# tarjeta2.net
KiCad netlist of a schematic drawn in EAGLE
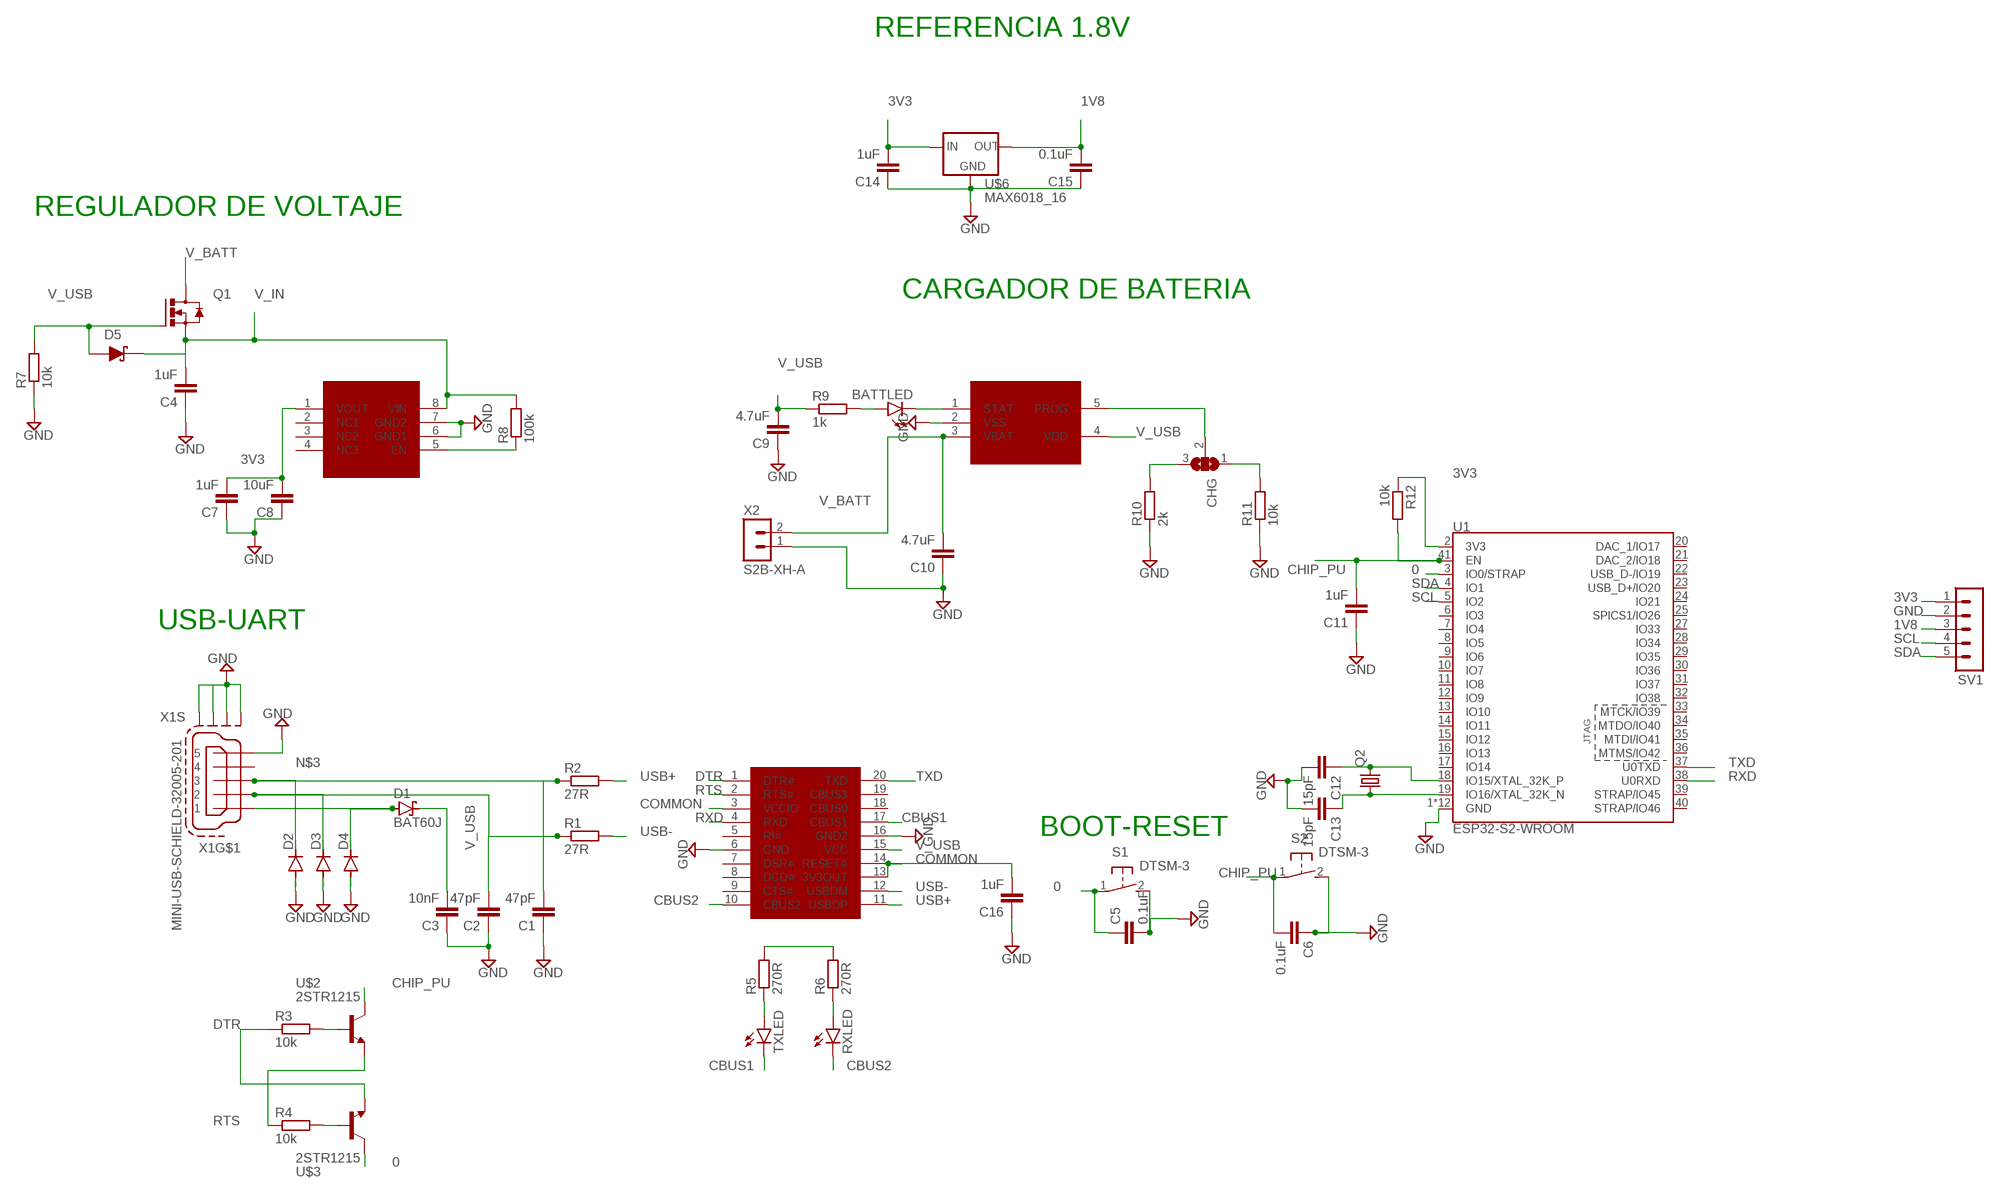
[diagram p0: schematic, sheet 1]

(export (version "E")
  (design (tool "Eeschema 10.0.6"))
  (components
    (comp (ref "BATTLED")
      (value "LEDSML0603")
      (footprint "eagle-import:SML0603")
      (libsource (lib "eagle-import") (part "LEDSML0603"))
    )
    (comp (ref "C1")
      (value "47pF")
      (footprint "eagle-import:C0805")
      (libsource (lib "eagle-import") (part "C-EUC0805"))
    )
    (comp (ref "C2")
      (value "47pF")
      (footprint "eagle-import:C0805")
      (libsource (lib "eagle-import") (part "C-EUC0805"))
    )
    (comp (ref "C3")
      (value "10nF")
      (footprint "eagle-import:C0805")
      (libsource (lib "eagle-import") (part "C-EUC0805"))
    )
    (comp (ref "C4")
      (value "1uF")
      (footprint "eagle-import:C0805")
      (libsource (lib "eagle-import") (part "C-EUC0805"))
    )
    (comp (ref "C5")
      (value "0.1uF")
      (footprint "eagle-import:C0805")
      (libsource (lib "eagle-import") (part "C-EUC0805"))
    )
    (comp (ref "C6")
      (value "0.1uF")
      (footprint "eagle-import:C0805")
      (libsource (lib "eagle-import") (part "C-EUC0805"))
    )
    (comp (ref "C7")
      (value "1uF")
      (footprint "eagle-import:C0805")
      (libsource (lib "eagle-import") (part "C-EUC0805"))
    )
    (comp (ref "C8")
      (value "10uF")
      (footprint "eagle-import:C0805")
      (libsource (lib "eagle-import") (part "C-EUC0805"))
    )
    (comp (ref "C9")
      (value "4.7uF")
      (footprint "eagle-import:C0805")
      (libsource (lib "eagle-import") (part "C-EUC0805"))
    )
    (comp (ref "C10")
      (value "4.7uF")
      (footprint "eagle-import:C0805")
      (libsource (lib "eagle-import") (part "C-EUC0805"))
    )
    (comp (ref "C11")
      (value "1uF")
      (footprint "eagle-import:C0805")
      (libsource (lib "eagle-import") (part "C-EUC0805"))
    )
    (comp (ref "C12")
      (value "15pF")
      (footprint "eagle-import:C0805")
      (libsource (lib "eagle-import") (part "C-EUC0805"))
    )
    (comp (ref "C13")
      (value "15pF")
      (footprint "eagle-import:C0805")
      (libsource (lib "eagle-import") (part "C-EUC0805"))
    )
    (comp (ref "C14")
      (value "1uF")
      (footprint "eagle-import:C0805")
      (libsource (lib "eagle-import") (part "C-EUC0805"))
    )
    (comp (ref "C15")
      (value "0.1uF")
      (footprint "eagle-import:C0805")
      (libsource (lib "eagle-import") (part "C-EUC0805"))
    )
    (comp (ref "C16")
      (value "1uF")
      (footprint "eagle-import:C0805")
      (libsource (lib "eagle-import") (part "C-EUC0805"))
    )
    (comp (ref "CHG")
      (value "SJ2W")
      (footprint "eagle-import:SJ_2")
      (libsource (lib "eagle-import") (part "SJ2W"))
    )
    (comp (ref "D1")
      (value "BAT60J")
      (footprint "eagle-import:SOD323_ST")
      (libsource (lib "eagle-import") (part "BAT60J"))
    )
    (comp (ref "D2")
      (value "DIODE-SOD523")
      (footprint "eagle-import:SOD523")
      (libsource (lib "eagle-import") (part "DIODE-SOD523"))
    )
    (comp (ref "D3")
      (value "DIODE-SOD523")
      (footprint "eagle-import:SOD523")
      (libsource (lib "eagle-import") (part "DIODE-SOD523"))
    )
    (comp (ref "D4")
      (value "DIODE-SOD523")
      (footprint "eagle-import:SOD523")
      (libsource (lib "eagle-import") (part "DIODE-SOD523"))
    )
    (comp (ref "D5")
      (value "D_SCHOTTKYK")
      (footprint "eagle-import:SOD-123")
      (libsource (lib "eagle-import") (part "D_SCHOTTKYK"))
    )
    (comp (ref "Q1")
      (value "MOSFET_N_SOT231")
      (footprint "eagle-import:SOT23")
      (libsource (lib "eagle-import") (part "MOSFET_N_SOT231"))
    )
    (comp (ref "Q2")
      (value "CRYSTALTC26V")
      (footprint "eagle-import:TC26V")
      (libsource (lib "eagle-import") (part "CRYSTALTC26V"))
    )
    (comp (ref "R1")
      (value "27R")
      (footprint "eagle-import:R0805")
      (libsource (lib "eagle-import") (part "R-EU_R0805"))
    )
    (comp (ref "R2")
      (value "27R")
      (footprint "eagle-import:R0805")
      (libsource (lib "eagle-import") (part "R-EU_R0805"))
    )
    (comp (ref "R3")
      (value "10k")
      (footprint "eagle-import:R0805")
      (libsource (lib "eagle-import") (part "R-EU_R0805"))
    )
    (comp (ref "R4")
      (value "10k")
      (footprint "eagle-import:R0805")
      (libsource (lib "eagle-import") (part "R-EU_R0805"))
    )
    (comp (ref "R5")
      (value "270R")
      (footprint "eagle-import:R0805")
      (libsource (lib "eagle-import") (part "R-EU_R0805"))
    )
    (comp (ref "R6")
      (value "270R")
      (footprint "eagle-import:R0805")
      (libsource (lib "eagle-import") (part "R-EU_R0805"))
    )
    (comp (ref "R7")
      (value "10k")
      (footprint "eagle-import:R0805")
      (libsource (lib "eagle-import") (part "R-EU_R0805"))
    )
    (comp (ref "R8")
      (value "100k")
      (footprint "eagle-import:R0805")
      (libsource (lib "eagle-import") (part "R-EU_R0805"))
    )
    (comp (ref "R9")
      (value "1k")
      (footprint "eagle-import:R0805")
      (libsource (lib "eagle-import") (part "R-EU_R0805"))
    )
    (comp (ref "R10")
      (value "2k")
      (footprint "eagle-import:R0805")
      (libsource (lib "eagle-import") (part "R-EU_R0805"))
    )
    (comp (ref "R11")
      (value "10k")
      (footprint "eagle-import:R0805")
      (libsource (lib "eagle-import") (part "R-EU_R0805"))
    )
    (comp (ref "R12")
      (value "10k")
      (footprint "eagle-import:R0805")
      (libsource (lib "eagle-import") (part "R-EU_R0805"))
    )
    (comp (ref "RXLED")
      (value "LEDSML0603")
      (footprint "eagle-import:SML0603")
      (libsource (lib "eagle-import") (part "LEDSML0603"))
    )
    (comp (ref "S1")
      (value "DTSM-3")
      (footprint "eagle-import:DTSM-3")
      (libsource (lib "eagle-import") (part "DTSM-3"))
    )
    (comp (ref "S2")
      (value "DTSM-3")
      (footprint "eagle-import:DTSM-3")
      (libsource (lib "eagle-import") (part "DTSM-3"))
    )
    (comp (ref "SV1")
      (value "MA05-1")
      (footprint "eagle-import:MA05-1")
      (libsource (lib "eagle-import") (part "MA05-1"))
    )
    (comp (ref "TXLED")
      (value "LEDSML0603")
      (footprint "eagle-import:SML0603")
      (libsource (lib "eagle-import") (part "LEDSML0603"))
    )
    (comp (ref "U$1")
      (value "FT231XS-R")
      (footprint "eagle-import:SSOP20")
      (libsource (lib "eagle-import") (part "FT231XS-R"))
    )
    (comp (ref "U$2")
      (value "2STR1215")
      (footprint "eagle-import:SOT23")
      (libsource (lib "eagle-import") (part "2STR1215"))
    )
    (comp (ref "U$3")
      (value "2STR1215")
      (footprint "eagle-import:SOT23")
      (libsource (lib "eagle-import") (part "2STR1215"))
    )
    (comp (ref "U$4")
      (value "AP2112-3.3")
      (footprint "eagle-import:SOIC8")
      (libsource (lib "eagle-import") (part "AP2112-3.3"))
    )
    (comp (ref "U$5")
      (value "MCP73831/2")
      (footprint "eagle-import:SOT23-5")
      (libsource (lib "eagle-import") (part "MCP73831/2"))
    )
    (comp (ref "U$6")
      (value "MAX6018_16")
      (footprint "eagle-import:SOT23")
      (libsource (lib "eagle-import") (part "MAX6018_16"))
    )
    (comp (ref "U1")
      (value "ESP32-S2-WROOM")
      (footprint "eagle-import:ESP32-S2-WROOM")
      (libsource (lib "eagle-import") (part "ESP32-S2-WROOM"))
    )
    (comp (ref "X1")
      (value "MINI-USB-SCHIELD-32005-201")
      (footprint "eagle-import:32005-201")
      (libsource (lib "eagle-import") (part "MINI-USB-SCHIELD-32005-201"))
    )
    (comp (ref "X2")
      (value "S2B-XH-A")
      (footprint "eagle-import:S2B-XH-A")
      (libsource (lib "eagle-import") (part "S2B-XH-A"))
    )
  )
  (nets
    (net (code "1") (name "/0") (class "Default")
      (node (ref "C5") (pin "1") (pinfunction "1_1") (pintype "passive"))
      (node (ref "S1") (pin "1") (pinfunction "1_1") (pintype "passive"))
      (node (ref "U$3") (pin "3") (pinfunction "C_3") (pintype "passive"))
      (node (ref "U1") (pin "3") (pinfunction "IO0/STRAP_3") (pintype "bidirectional"))
    )
    (net (code "2") (name "/1V8") (class "Default")
      (node (ref "C15") (pin "2") (pinfunction "2_2") (pintype "passive"))
      (node (ref "SV1") (pin "3") (pinfunction "3_3") (pintype "passive"))
      (node (ref "U$6") (pin "2") (pinfunction "OUT_2") (pintype "passive"))
    )
    (net (code "3") (name "/3V3") (class "Default")
      (node (ref "C14") (pin "2") (pinfunction "2_2") (pintype "passive"))
      (node (ref "C7") (pin "2") (pinfunction "2_2") (pintype "passive"))
      (node (ref "C8") (pin "2") (pinfunction "2_2") (pintype "passive"))
      (node (ref "R12") (pin "1") (pinfunction "1_1") (pintype "passive"))
      (node (ref "SV1") (pin "1") (pinfunction "1_1") (pintype "passive"))
      (node (ref "U$4") (pin "1") (pinfunction "VOUT_1") (pintype "bidirectional"))
      (node (ref "U$6") (pin "1") (pinfunction "IN_1") (pintype "input"))
      (node (ref "U1") (pin "2") (pinfunction "3V3_2") (pintype "bidirectional"))
    )
    (net (code "4") (name "/CBUS1") (class "Default")
      (node (ref "TXLED") (pin "C") (pinfunction "C_C") (pintype "passive"))
      (node (ref "U$1") (pin "17") (pinfunction "CBUS1_17") (pintype "bidirectional"))
    )
    (net (code "5") (name "/CBUS2") (class "Default")
      (node (ref "RXLED") (pin "C") (pinfunction "C_C") (pintype "passive"))
      (node (ref "U$1") (pin "10") (pinfunction "CBUS2_10") (pintype "bidirectional"))
    )
    (net (code "6") (name "/CHIP_PU") (class "Default")
      (node (ref "C11") (pin "2") (pinfunction "2_2") (pintype "passive"))
      (node (ref "C6") (pin "2") (pinfunction "2_2") (pintype "passive"))
      (node (ref "R12") (pin "2") (pinfunction "2_2") (pintype "passive"))
      (node (ref "S2") (pin "1") (pinfunction "1_1") (pintype "passive"))
      (node (ref "U$2") (pin "3") (pinfunction "C_3") (pintype "passive"))
      (node (ref "U1") (pin "41") (pinfunction "EN_41") (pintype "bidirectional"))
    )
    (net (code "7") (name "/COMMON") (class "Default")
      (node (ref "C16") (pin "2") (pinfunction "2_2") (pintype "passive"))
      (node (ref "U$1") (pin "13") (pinfunction "3V3OUT_13") (pintype "bidirectional"))
      (node (ref "U$1") (pin "14") (pinfunction "RESET#_14") (pintype "bidirectional"))
      (node (ref "U$1") (pin "3") (pinfunction "VCCIO_3") (pintype "bidirectional"))
    )
    (net (code "8") (name "/DTR") (class "Default")
      (node (ref "R3") (pin "1") (pinfunction "1_1") (pintype "passive"))
      (node (ref "U$1") (pin "1") (pinfunction "DTR#_1") (pintype "bidirectional"))
      (node (ref "U$3") (pin "2") (pinfunction "E_2") (pintype "passive"))
    )
    (net (code "9") (name "/N$3") (class "Default")
      (node (ref "C1") (pin "2") (pinfunction "2_2") (pintype "passive"))
      (node (ref "D2") (pin "C") (pinfunction "C_C") (pintype "passive"))
      (node (ref "R2") (pin "1") (pinfunction "1_1") (pintype "passive"))
      (node (ref "X1") (pin "3") (pinfunction "3_3") (pintype "passive"))
    )
    (net (code "10") (name "/RTS") (class "Default")
      (node (ref "R4") (pin "1") (pinfunction "1_1") (pintype "passive"))
      (node (ref "U$1") (pin "2") (pinfunction "RTS#_2") (pintype "bidirectional"))
      (node (ref "U$2") (pin "2") (pinfunction "E_2") (pintype "passive"))
    )
    (net (code "11") (name "/RXD") (class "Default")
      (node (ref "U$1") (pin "4") (pinfunction "RXD_4") (pintype "bidirectional"))
      (node (ref "U1") (pin "38") (pinfunction "U0RXD_38") (pintype "bidirectional"))
    )
    (net (code "12") (name "/SCL") (class "Default")
      (node (ref "SV1") (pin "4") (pinfunction "4_4") (pintype "passive"))
      (node (ref "U1") (pin "5") (pinfunction "IO2_5") (pintype "bidirectional"))
    )
    (net (code "13") (name "/SDA") (class "Default")
      (node (ref "SV1") (pin "5") (pinfunction "5_5") (pintype "passive"))
      (node (ref "U1") (pin "4") (pinfunction "IO1_4") (pintype "bidirectional"))
    )
    (net (code "14") (name "/TXD") (class "Default")
      (node (ref "U$1") (pin "20") (pinfunction "TXD_20") (pintype "bidirectional"))
      (node (ref "U1") (pin "37") (pinfunction "U0TXD_37") (pintype "bidirectional"))
    )
    (net (code "15") (name "/USB+") (class "Default")
      (node (ref "R2") (pin "2") (pinfunction "2_2") (pintype "passive"))
      (node (ref "U$1") (pin "11") (pinfunction "USBDP_11") (pintype "bidirectional"))
    )
    (net (code "16") (name "/USB-") (class "Default")
      (node (ref "R1") (pin "2") (pinfunction "2_2") (pintype "passive"))
      (node (ref "U$1") (pin "12") (pinfunction "USBDM_12") (pintype "bidirectional"))
    )
    (net (code "17") (name "/V_BATT") (class "Default")
      (node (ref "C10") (pin "2") (pinfunction "2_2") (pintype "passive"))
      (node (ref "Q1") (pin "3") (pinfunction "D_3") (pintype "passive"))
      (node (ref "U$5") (pin "3") (pinfunction "VBAT_3") (pintype "bidirectional"))
      (node (ref "X2") (pin "2") (pinfunction "2_2") (pintype "passive"))
    )
    (net (code "18") (name "/V_IN") (class "Default")
      (node (ref "C4") (pin "2") (pinfunction "2_2") (pintype "passive"))
      (node (ref "D5") (pin "2") (pinfunction "C_2") (pintype "passive"))
      (node (ref "Q1") (pin "2") (pinfunction "S_2") (pintype "passive"))
      (node (ref "R8") (pin "2") (pinfunction "2_2") (pintype "passive"))
      (node (ref "U$4") (pin "8") (pinfunction "VIN_8") (pintype "bidirectional"))
    )
    (net (code "19") (name "/V_USB") (class "Default")
      (node (ref "C3") (pin "2") (pinfunction "2_2") (pintype "passive"))
      (node (ref "C9") (pin "2") (pinfunction "2_2") (pintype "passive"))
      (node (ref "D1") (pin "C") (pinfunction "C_C") (pintype "passive"))
      (node (ref "D5") (pin "1") (pinfunction "A_1") (pintype "passive"))
      (node (ref "Q1") (pin "1") (pinfunction "G_1") (pintype "passive"))
      (node (ref "R5") (pin "2") (pinfunction "2_2") (pintype "passive"))
      (node (ref "R6") (pin "2") (pinfunction "2_2") (pintype "passive"))
      (node (ref "R7") (pin "2") (pinfunction "2_2") (pintype "passive"))
      (node (ref "R9") (pin "1") (pinfunction "1_1") (pintype "passive"))
      (node (ref "U$1") (pin "15") (pinfunction "VCC_15") (pintype "bidirectional"))
      (node (ref "U$5") (pin "4") (pinfunction "VDD_4") (pintype "bidirectional"))
    )
    (net (code "20") (name "GND") (class "Default")
      (node (ref "C1") (pin "1") (pinfunction "1_1") (pintype "passive"))
      (node (ref "C10") (pin "1") (pinfunction "1_1") (pintype "passive"))
      (node (ref "C11") (pin "1") (pinfunction "1_1") (pintype "passive"))
      (node (ref "C12") (pin "2") (pinfunction "2_2") (pintype "passive"))
      (node (ref "C13") (pin "2") (pinfunction "2_2") (pintype "passive"))
      (node (ref "C14") (pin "1") (pinfunction "1_1") (pintype "passive"))
      (node (ref "C15") (pin "1") (pinfunction "1_1") (pintype "passive"))
      (node (ref "C16") (pin "1") (pinfunction "1_1") (pintype "passive"))
      (node (ref "C2") (pin "1") (pinfunction "1_1") (pintype "passive"))
      (node (ref "C3") (pin "1") (pinfunction "1_1") (pintype "passive"))
      (node (ref "C4") (pin "1") (pinfunction "1_1") (pintype "passive"))
      (node (ref "C5") (pin "2") (pinfunction "2_2") (pintype "passive"))
      (node (ref "C6") (pin "1") (pinfunction "1_1") (pintype "passive"))
      (node (ref "C7") (pin "1") (pinfunction "1_1") (pintype "passive"))
      (node (ref "C8") (pin "1") (pinfunction "1_1") (pintype "passive"))
      (node (ref "C9") (pin "1") (pinfunction "1_1") (pintype "passive"))
      (node (ref "D2") (pin "A") (pinfunction "A_A") (pintype "passive"))
      (node (ref "D3") (pin "A") (pinfunction "A_A") (pintype "passive"))
      (node (ref "D4") (pin "A") (pinfunction "A_A") (pintype "passive"))
      (node (ref "R10") (pin "1") (pinfunction "1_1") (pintype "passive"))
      (node (ref "R11") (pin "1") (pinfunction "1_1") (pintype "passive"))
      (node (ref "R7") (pin "1") (pinfunction "1_1") (pintype "passive"))
      (node (ref "S1") (pin "2") (pinfunction "2_2") (pintype "passive"))
      (node (ref "S2") (pin "2") (pinfunction "2_2") (pintype "passive"))
      (node (ref "SV1") (pin "2") (pinfunction "2_2") (pintype "passive"))
      (node (ref "U$1") (pin "16") (pinfunction "GND2_16") (pintype "bidirectional"))
      (node (ref "U$1") (pin "6") (pinfunction "GND_6") (pintype "bidirectional"))
      (node (ref "U$4") (pin "6") (pinfunction "GND1_6") (pintype "bidirectional"))
      (node (ref "U$4") (pin "7") (pinfunction "GND2_7") (pintype "bidirectional"))
      (node (ref "U$5") (pin "2") (pinfunction "VSS_2") (pintype "bidirectional"))
      (node (ref "U$6") (pin "3") (pinfunction "GND_3") (pintype "input"))
      (node (ref "U1") (pin "1") (pinfunction "GND_1") (pintype "bidirectional"))
      (node (ref "U1") (pin "26") (pinfunction "GND_26") (pintype "bidirectional"))
      (node (ref "U1") (pin "42") (pinfunction "GND_42") (pintype "bidirectional"))
      (node (ref "U1") (pin "GNDEP0") (pinfunction "GND_GNDEP0") (pintype "bidirectional"))
      (node (ref "U1") (pin "GNDEP1") (pinfunction "GND_GNDEP1") (pintype "bidirectional"))
      (node (ref "U1") (pin "GNDEP2") (pinfunction "GND_GNDEP2") (pintype "bidirectional"))
      (node (ref "U1") (pin "GNDEP3") (pinfunction "GND_GNDEP3") (pintype "bidirectional"))
      (node (ref "U1") (pin "GNDEP4") (pinfunction "GND_GNDEP4") (pintype "bidirectional"))
      (node (ref "U1") (pin "GNDEP5") (pinfunction "GND_GNDEP5") (pintype "bidirectional"))
      (node (ref "U1") (pin "GNDEP6") (pinfunction "GND_GNDEP6") (pintype "bidirectional"))
      (node (ref "U1") (pin "GNDEP7") (pinfunction "GND_GNDEP7") (pintype "bidirectional"))
      (node (ref "U1") (pin "GNDEP8") (pinfunction "GND_GNDEP8") (pintype "bidirectional"))
      (node (ref "X1") (pin "5") (pinfunction "5_5") (pintype "passive"))
      (node (ref "X1") (pin "M1") (pinfunction "S1_M1") (pintype "passive"))
      (node (ref "X1") (pin "M2") (pinfunction "S2_M2") (pintype "passive"))
      (node (ref "X1") (pin "M3") (pinfunction "S3_M3") (pintype "passive"))
      (node (ref "X1") (pin "M4") (pinfunction "S4_M4") (pintype "passive"))
      (node (ref "X2") (pin "1") (pinfunction "1_1") (pintype "passive"))
    )
    (net (code "21") (name "Net-(BATTLED-PadA)") (class "Default")
      (node (ref "BATTLED") (pin "A") (pinfunction "A_A") (pintype "passive"))
      (node (ref "R9") (pin "2") (pinfunction "2_2") (pintype "passive"))
    )
    (net (code "22") (name "Net-(C2-Pad2)") (class "Default")
      (node (ref "C2") (pin "2") (pinfunction "2_2") (pintype "passive"))
      (node (ref "D3") (pin "C") (pinfunction "C_C") (pintype "passive"))
      (node (ref "R1") (pin "1") (pinfunction "1_1") (pintype "passive"))
      (node (ref "X1") (pin "2") (pinfunction "2_2") (pintype "passive"))
    )
    (net (code "23") (name "Net-(CHG-Pad1)") (class "Default")
      (node (ref "CHG") (pin "1") (pinfunction "1_1") (pintype "passive"))
      (node (ref "R11") (pin "2") (pinfunction "2_2") (pintype "passive"))
    )
    (net (code "24") (name "Net-(CHG-Pad3)") (class "Default")
      (node (ref "CHG") (pin "3") (pinfunction "3_3") (pintype "passive"))
      (node (ref "R10") (pin "2") (pinfunction "2_2") (pintype "passive"))
    )
    (net (code "25") (name "Net-(D1-PadA)") (class "Default")
      (node (ref "D1") (pin "A") (pinfunction "A_A") (pintype "passive"))
      (node (ref "D4") (pin "C") (pinfunction "C_C") (pintype "passive"))
      (node (ref "X1") (pin "1") (pinfunction "1_1") (pintype "passive"))
    )
    (net (code "26") (name "Net-(R5-Pad1)") (class "Default")
      (node (ref "R5") (pin "1") (pinfunction "1_1") (pintype "passive"))
      (node (ref "TXLED") (pin "A") (pinfunction "A_A") (pintype "passive"))
    )
    (net (code "27") (name "Net-(R6-Pad1)") (class "Default")
      (node (ref "R6") (pin "1") (pinfunction "1_1") (pintype "passive"))
      (node (ref "RXLED") (pin "A") (pinfunction "A_A") (pintype "passive"))
    )
    (net (code "28") (name "Net-(U$2-B)") (class "Default")
      (node (ref "R3") (pin "2") (pinfunction "2_2") (pintype "passive"))
      (node (ref "U$2") (pin "1") (pinfunction "B_1") (pintype "passive"))
    )
    (net (code "29") (name "Net-(U$3-B)") (class "Default")
      (node (ref "R4") (pin "2") (pinfunction "2_2") (pintype "passive"))
      (node (ref "U$3") (pin "1") (pinfunction "B_1") (pintype "passive"))
    )
    (net (code "30") (name "Net-(U$4-EN)") (class "Default")
      (node (ref "R8") (pin "1") (pinfunction "1_1") (pintype "passive"))
      (node (ref "U$4") (pin "5") (pinfunction "EN_5") (pintype "bidirectional"))
    )
    (net (code "31") (name "Net-(U$5-PROG)") (class "Default")
      (node (ref "CHG") (pin "2") (pinfunction "2_2") (pintype "passive"))
      (node (ref "U$5") (pin "5") (pinfunction "PROG_5") (pintype "bidirectional"))
    )
    (net (code "32") (name "Net-(U$5-STAT)") (class "Default")
      (node (ref "BATTLED") (pin "C") (pinfunction "C_C") (pintype "passive"))
      (node (ref "U$5") (pin "1") (pinfunction "STAT_1") (pintype "bidirectional"))
    )
    (net (code "33") (name "Net-(U1-IO15{slash}XTAL_32K_P)") (class "Default")
      (node (ref "C12") (pin "1") (pinfunction "1_1") (pintype "passive"))
      (node (ref "Q2") (pin "2") (pinfunction "2_2") (pintype "passive"))
      (node (ref "U1") (pin "18") (pinfunction "IO15/XTAL_32K_P_18") (pintype "bidirectional"))
    )
    (net (code "34") (name "Net-(U1-IO16{slash}XTAL_32K_N)") (class "Default")
      (node (ref "C13") (pin "1") (pinfunction "1_1") (pintype "passive"))
      (node (ref "Q2") (pin "1") (pinfunction "1_1") (pintype "passive"))
      (node (ref "U1") (pin "19") (pinfunction "IO16/XTAL_32K_N_19") (pintype "bidirectional"))
    )
    (net (code "35") (name "unconnected-(U$1-CBUS0-Pad18)") (class "Default")
      (node (ref "U$1") (pin "18") (pinfunction "CBUS0_18") (pintype "bidirectional"))
    )
    (net (code "36") (name "unconnected-(U$1-CBUS3-Pad19)") (class "Default")
      (node (ref "U$1") (pin "19") (pinfunction "CBUS3_19") (pintype "bidirectional"))
    )
    (net (code "37") (name "unconnected-(U$1-CTS#-Pad9)") (class "Default")
      (node (ref "U$1") (pin "9") (pinfunction "CTS#_9") (pintype "bidirectional"))
    )
    (net (code "38") (name "unconnected-(U$1-DCD#-Pad8)") (class "Default")
      (node (ref "U$1") (pin "8") (pinfunction "DCD#_8") (pintype "bidirectional"))
    )
    (net (code "39") (name "unconnected-(U$1-DSR#-Pad7)") (class "Default")
      (node (ref "U$1") (pin "7") (pinfunction "DSR#_7") (pintype "bidirectional"))
    )
    (net (code "40") (name "unconnected-(U$1-RI#-Pad5)") (class "Default")
      (node (ref "U$1") (pin "5") (pinfunction "RI#_5") (pintype "bidirectional"))
    )
    (net (code "41") (name "unconnected-(U$4-NC1-Pad2)") (class "Default")
      (node (ref "U$4") (pin "2") (pinfunction "NC1_2") (pintype "bidirectional"))
    )
    (net (code "42") (name "unconnected-(U$4-NC2-Pad3)") (class "Default")
      (node (ref "U$4") (pin "3") (pinfunction "NC2_3") (pintype "bidirectional"))
    )
    (net (code "43") (name "unconnected-(U$4-NC3-Pad4)") (class "Default")
      (node (ref "U$4") (pin "4") (pinfunction "NC3_4") (pintype "bidirectional"))
    )
    (net (code "44") (name "unconnected-(U1-DAC_1{slash}IO17-Pad20)") (class "Default")
      (node (ref "U1") (pin "20") (pinfunction "DAC_1/IO17_20") (pintype "bidirectional"))
    )
    (net (code "45") (name "unconnected-(U1-DAC_2{slash}IO18-Pad21)") (class "Default")
      (node (ref "U1") (pin "21") (pinfunction "DAC_2/IO18_21") (pintype "bidirectional"))
    )
    (net (code "46") (name "unconnected-(U1-IO3-Pad6)") (class "Default")
      (node (ref "U1") (pin "6") (pinfunction "IO3_6") (pintype "bidirectional"))
    )
    (net (code "47") (name "unconnected-(U1-IO4-Pad7)") (class "Default")
      (node (ref "U1") (pin "7") (pinfunction "IO4_7") (pintype "bidirectional"))
    )
    (net (code "48") (name "unconnected-(U1-IO5-Pad8)") (class "Default")
      (node (ref "U1") (pin "8") (pinfunction "IO5_8") (pintype "bidirectional"))
    )
    (net (code "49") (name "unconnected-(U1-IO6-Pad9)") (class "Default")
      (node (ref "U1") (pin "9") (pinfunction "IO6_9") (pintype "bidirectional"))
    )
    (net (code "50") (name "unconnected-(U1-IO7-Pad10)") (class "Default")
      (node (ref "U1") (pin "10") (pinfunction "IO7_10") (pintype "bidirectional"))
    )
    (net (code "51") (name "unconnected-(U1-IO8-Pad11)") (class "Default")
      (node (ref "U1") (pin "11") (pinfunction "IO8_11") (pintype "bidirectional"))
    )
    (net (code "52") (name "unconnected-(U1-IO9-Pad12)") (class "Default")
      (node (ref "U1") (pin "12") (pinfunction "IO9_12") (pintype "bidirectional"))
    )
    (net (code "53") (name "unconnected-(U1-IO10-Pad13)") (class "Default")
      (node (ref "U1") (pin "13") (pinfunction "IO10_13") (pintype "bidirectional"))
    )
    (net (code "54") (name "unconnected-(U1-IO11-Pad14)") (class "Default")
      (node (ref "U1") (pin "14") (pinfunction "IO11_14") (pintype "bidirectional"))
    )
    (net (code "55") (name "unconnected-(U1-IO12-Pad15)") (class "Default")
      (node (ref "U1") (pin "15") (pinfunction "IO12_15") (pintype "bidirectional"))
    )
    (net (code "56") (name "unconnected-(U1-IO13-Pad16)") (class "Default")
      (node (ref "U1") (pin "16") (pinfunction "IO13_16") (pintype "bidirectional"))
    )
    (net (code "57") (name "unconnected-(U1-IO14-Pad17)") (class "Default")
      (node (ref "U1") (pin "17") (pinfunction "IO14_17") (pintype "bidirectional"))
    )
    (net (code "58") (name "unconnected-(U1-IO21-Pad24)") (class "Default")
      (node (ref "U1") (pin "24") (pinfunction "IO21_24") (pintype "bidirectional"))
    )
    (net (code "59") (name "unconnected-(U1-IO33-Pad27)") (class "Default")
      (node (ref "U1") (pin "27") (pinfunction "IO33_27") (pintype "bidirectional"))
    )
    (net (code "60") (name "unconnected-(U1-IO34-Pad28)") (class "Default")
      (node (ref "U1") (pin "28") (pinfunction "IO34_28") (pintype "bidirectional"))
    )
    (net (code "61") (name "unconnected-(U1-IO35-Pad29)") (class "Default")
      (node (ref "U1") (pin "29") (pinfunction "IO35_29") (pintype "bidirectional"))
    )
    (net (code "62") (name "unconnected-(U1-IO36-Pad30)") (class "Default")
      (node (ref "U1") (pin "30") (pinfunction "IO36_30") (pintype "bidirectional"))
    )
    (net (code "63") (name "unconnected-(U1-IO37-Pad31)") (class "Default")
      (node (ref "U1") (pin "31") (pinfunction "IO37_31") (pintype "bidirectional"))
    )
    (net (code "64") (name "unconnected-(U1-IO38-Pad32)") (class "Default")
      (node (ref "U1") (pin "32") (pinfunction "IO38_32") (pintype "bidirectional"))
    )
    (net (code "65") (name "unconnected-(U1-MTCK{slash}IO39-Pad33)") (class "Default")
      (node (ref "U1") (pin "33") (pinfunction "MTCK/IO39_33") (pintype "bidirectional"))
    )
    (net (code "66") (name "unconnected-(U1-MTDI{slash}IO41-Pad35)") (class "Default")
      (node (ref "U1") (pin "35") (pinfunction "MTDI/IO41_35") (pintype "bidirectional"))
    )
    (net (code "67") (name "unconnected-(U1-MTDO{slash}IO40-Pad34)") (class "Default")
      (node (ref "U1") (pin "34") (pinfunction "MTDO/IO40_34") (pintype "bidirectional"))
    )
    (net (code "68") (name "unconnected-(U1-MTMS{slash}IO42-Pad36)") (class "Default")
      (node (ref "U1") (pin "36") (pinfunction "MTMS/IO42_36") (pintype "bidirectional"))
    )
    (net (code "69") (name "unconnected-(U1-SPICS1{slash}IO26-Pad25)") (class "Default")
      (node (ref "U1") (pin "25") (pinfunction "SPICS1/IO26_25") (pintype "bidirectional"))
    )
    (net (code "70") (name "unconnected-(U1-STRAP{slash}IO45-Pad39)") (class "Default")
      (node (ref "U1") (pin "39") (pinfunction "STRAP/IO45_39") (pintype "bidirectional"))
    )
    (net (code "71") (name "unconnected-(U1-STRAP{slash}IO46-Pad40)") (class "Default")
      (node (ref "U1") (pin "40") (pinfunction "STRAP/IO46_40") (pintype "bidirectional"))
    )
    (net (code "72") (name "unconnected-(U1-USB_D+{slash}IO20-Pad23)") (class "Default")
      (node (ref "U1") (pin "23") (pinfunction "USB_D+/IO20_23") (pintype "bidirectional"))
    )
    (net (code "73") (name "unconnected-(U1-USB_D-{slash}IO19-Pad22)") (class "Default")
      (node (ref "U1") (pin "22") (pinfunction "USB_D-/IO19_22") (pintype "bidirectional"))
    )
    (net (code "74") (name "unconnected-(X1-Pad4)") (class "Default")
      (node (ref "X1") (pin "4") (pinfunction "4_4") (pintype "passive"))
    )
  )
)
